# Environment-ArduinoNano44-Mini-Enclosure.net
KiCad netlist of a schematic drawn in EAGLE
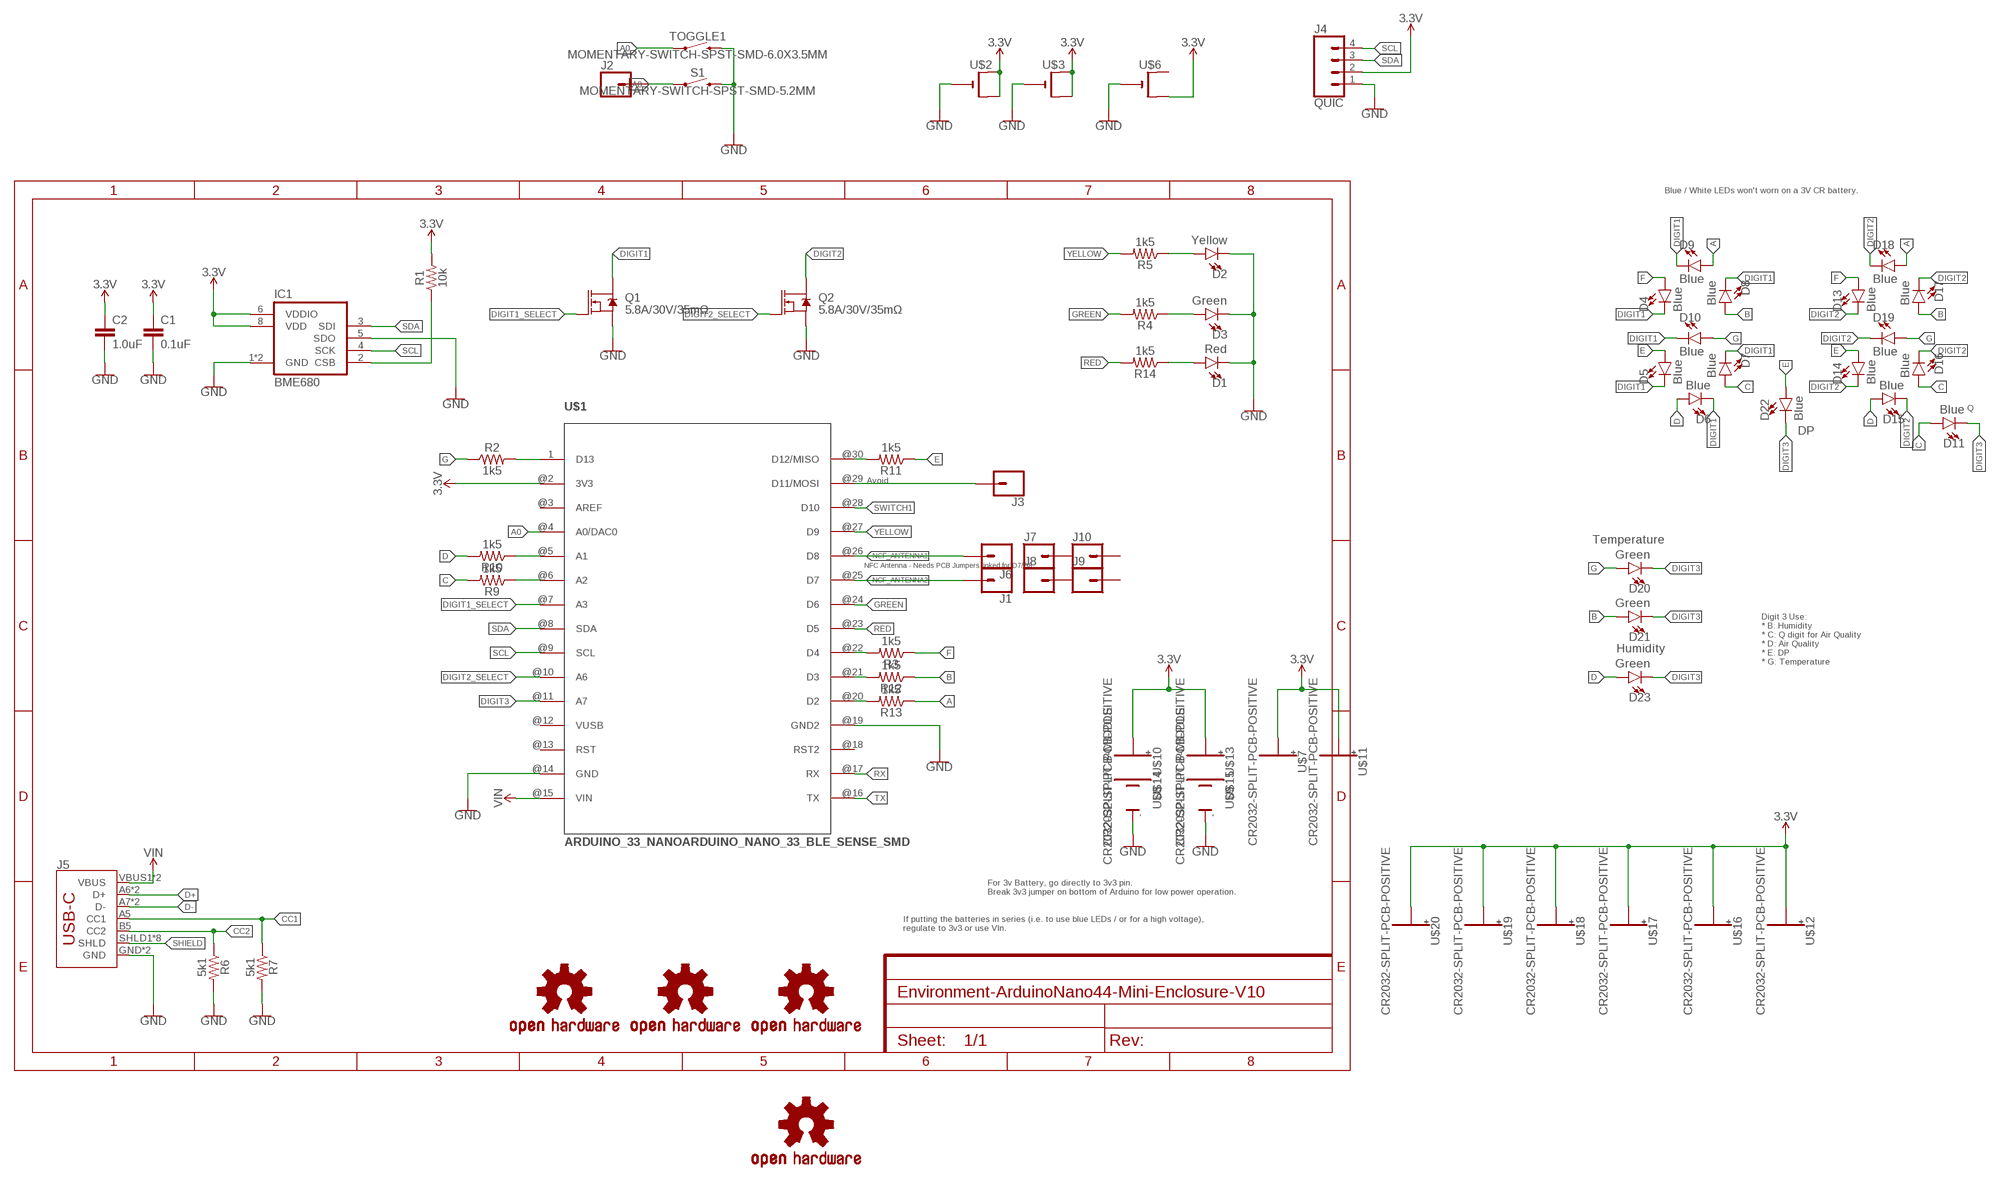
[diagram p0: schematic, sheet 1]

(export (version "E")
  (design (tool "Eeschema 10.0.6"))
  (components
    (comp (ref "C1")
      (value "0.1uF")
      (footprint "eagle-import:0805")
      (libsource (lib "eagle-import") (part "0.1UF-0805-25V"))
    )
    (comp (ref "C2")
      (value "1.0uF")
      (footprint "eagle-import:0805")
      (libsource (lib "eagle-import") (part "1.0UF-0805-25V-10%"))
    )
    (comp (ref "D1")
      (value "Red")
      (footprint "eagle-import:LED-1206")
      (libsource (lib "eagle-import") (part "LED1206"))
    )
    (comp (ref "D2")
      (value "Yellow")
      (footprint "eagle-import:LED-1206")
      (libsource (lib "eagle-import") (part "LED1206"))
    )
    (comp (ref "D3")
      (value "Green")
      (footprint "eagle-import:LED-1206")
      (libsource (lib "eagle-import") (part "LED1206"))
    )
    (comp (ref "D4")
      (value "Blue")
      (footprint "eagle-import:LED-1206")
      (libsource (lib "eagle-import") (part "LED1206"))
    )
    (comp (ref "D5")
      (value "Blue")
      (footprint "eagle-import:LED-1206")
      (libsource (lib "eagle-import") (part "LED1206"))
    )
    (comp (ref "D6")
      (value "Blue")
      (footprint "eagle-import:LED-1206")
      (libsource (lib "eagle-import") (part "LED1206"))
    )
    (comp (ref "D7")
      (value "Blue")
      (footprint "eagle-import:LED-1206")
      (libsource (lib "eagle-import") (part "LED1206"))
    )
    (comp (ref "D8")
      (value "Blue")
      (footprint "eagle-import:LED-1206")
      (libsource (lib "eagle-import") (part "LED1206"))
    )
    (comp (ref "D9")
      (value "Blue")
      (footprint "eagle-import:LED-1206")
      (libsource (lib "eagle-import") (part "LED1206"))
    )
    (comp (ref "D10")
      (value "Blue")
      (footprint "eagle-import:LED-1206")
      (libsource (lib "eagle-import") (part "LED1206"))
    )
    (comp (ref "D11")
      (value "Blue")
      (footprint "eagle-import:LED-1206")
      (libsource (lib "eagle-import") (part "LED1206"))
    )
    (comp (ref "D13")
      (value "Blue")
      (footprint "eagle-import:LED-1206")
      (libsource (lib "eagle-import") (part "LED1206"))
    )
    (comp (ref "D14")
      (value "Blue")
      (footprint "eagle-import:LED-1206")
      (libsource (lib "eagle-import") (part "LED1206"))
    )
    (comp (ref "D15")
      (value "Blue")
      (footprint "eagle-import:LED-1206")
      (libsource (lib "eagle-import") (part "LED1206"))
    )
    (comp (ref "D16")
      (value "Blue")
      (footprint "eagle-import:LED-1206")
      (libsource (lib "eagle-import") (part "LED1206"))
    )
    (comp (ref "D17")
      (value "Blue")
      (footprint "eagle-import:LED-1206")
      (libsource (lib "eagle-import") (part "LED1206"))
    )
    (comp (ref "D18")
      (value "Blue")
      (footprint "eagle-import:LED-1206")
      (libsource (lib "eagle-import") (part "LED1206"))
    )
    (comp (ref "D19")
      (value "Blue")
      (footprint "eagle-import:LED-1206")
      (libsource (lib "eagle-import") (part "LED1206"))
    )
    (comp (ref "D20")
      (value "Green")
      (footprint "eagle-import:LED-1206")
      (libsource (lib "eagle-import") (part "LED1206"))
    )
    (comp (ref "D21")
      (value "Green")
      (footprint "eagle-import:LED-1206")
      (libsource (lib "eagle-import") (part "LED1206"))
    )
    (comp (ref "D22")
      (value "Blue")
      (footprint "eagle-import:LED-1206")
      (libsource (lib "eagle-import") (part "LED1206"))
    )
    (comp (ref "D23")
      (value "Green")
      (footprint "eagle-import:LED-1206")
      (libsource (lib "eagle-import") (part "LED1206"))
    )
    (comp (ref "IC1")
      (value "BME680")
      (footprint "eagle-import:BME680")
      (libsource (lib "eagle-import") (part "BME680"))
    )
    (comp (ref "J1")
      (value "CONN_01")
      (footprint "eagle-import:1X01")
      (libsource (lib "eagle-import") (part "CONN_01"))
    )
    (comp (ref "J2")
      (value "CONN_01")
      (footprint "eagle-import:1X01")
      (libsource (lib "eagle-import") (part "CONN_01"))
    )
    (comp (ref "J3")
      (value "CONN_01")
      (footprint "eagle-import:1X01")
      (libsource (lib "eagle-import") (part "CONN_01"))
    )
    (comp (ref "J4")
      (value "QUIC")
      (footprint "eagle-import:JST04_1MM_RA")
      (libsource (lib "eagle-import") (part "CONN_04SMD2"))
    )
    (comp (ref "J5")
      (value "USB_C2-LAYER")
      (footprint "eagle-import:USB-C-16P")
      (libsource (lib "eagle-import") (part "USB_C2-LAYER"))
    )
    (comp (ref "J6")
      (value "CONN_01")
      (footprint "eagle-import:1X01")
      (libsource (lib "eagle-import") (part "CONN_01"))
    )
    (comp (ref "J7")
      (value "CONN_01")
      (footprint "eagle-import:1X01")
      (libsource (lib "eagle-import") (part "CONN_01"))
    )
    (comp (ref "J8")
      (value "CONN_01")
      (footprint "eagle-import:1X01")
      (libsource (lib "eagle-import") (part "CONN_01"))
    )
    (comp (ref "J9")
      (value "CONN_01")
      (footprint "eagle-import:1X01")
      (libsource (lib "eagle-import") (part "CONN_01"))
    )
    (comp (ref "J10")
      (value "CONN_01")
      (footprint "eagle-import:1X01")
      (libsource (lib "eagle-import") (part "CONN_01"))
    )
    (comp (ref "LOGO1")
      (value "OSHW-LOGOM")
      (footprint "eagle-import:OSHW-LOGO-M")
      (libsource (lib "eagle-import") (part "OSHW-LOGOM"))
    )
    (comp (ref "LOGO2")
      (value "OSHW-LOGOL")
      (footprint "eagle-import:OSHW-LOGO-L")
      (libsource (lib "eagle-import") (part "OSHW-LOGOL"))
    )
    (comp (ref "LOGO3")
      (value "OSHW-LOGOL")
      (footprint "eagle-import:OSHW-LOGO-L")
      (libsource (lib "eagle-import") (part "OSHW-LOGOL"))
    )
    (comp (ref "LOGO7")
      (value "OSHW-LOGOM")
      (footprint "eagle-import:OSHW-LOGO-M")
      (libsource (lib "eagle-import") (part "OSHW-LOGOM"))
    )
    (comp (ref "Q1")
      (value "5.8A/30V/35mΩ")
      (footprint "eagle-import:SOT23-3")
      (libsource (lib "eagle-import") (part "MOSFET-NCH-AO3404A"))
    )
    (comp (ref "Q2")
      (value "5.8A/30V/35mΩ")
      (footprint "eagle-import:SOT23-3")
      (libsource (lib "eagle-import") (part "MOSFET-NCH-AO3404A"))
    )
    (comp (ref "R1")
      (value "10k")
      (footprint "eagle-import:0805")
      (libsource (lib "eagle-import") (part "RESISTOR0805"))
    )
    (comp (ref "R2")
      (value "1k5")
      (footprint "eagle-import:0805")
      (libsource (lib "eagle-import") (part "RESISTOR0805"))
    )
    (comp (ref "R3")
      (value "1k5")
      (footprint "eagle-import:0805")
      (libsource (lib "eagle-import") (part "RESISTOR0805"))
    )
    (comp (ref "R4")
      (value "1k5")
      (footprint "eagle-import:0805")
      (libsource (lib "eagle-import") (part "RESISTOR0805"))
    )
    (comp (ref "R5")
      (value "1k5")
      (footprint "eagle-import:0805")
      (libsource (lib "eagle-import") (part "RESISTOR0805"))
    )
    (comp (ref "R6")
      (value "5k1")
      (footprint "eagle-import:0805")
      (libsource (lib "eagle-import") (part "RESISTOR0805"))
    )
    (comp (ref "R7")
      (value "5k1")
      (footprint "eagle-import:0805")
      (libsource (lib "eagle-import") (part "RESISTOR0805"))
    )
    (comp (ref "R9")
      (value "1k5")
      (footprint "eagle-import:0805")
      (libsource (lib "eagle-import") (part "RESISTOR0805"))
    )
    (comp (ref "R10")
      (value "1k5")
      (footprint "eagle-import:0805")
      (libsource (lib "eagle-import") (part "RESISTOR0805"))
    )
    (comp (ref "R11")
      (value "1k5")
      (footprint "eagle-import:0805")
      (libsource (lib "eagle-import") (part "RESISTOR0805"))
    )
    (comp (ref "R12")
      (value "1k5")
      (footprint "eagle-import:0805")
      (libsource (lib "eagle-import") (part "RESISTOR0805"))
    )
    (comp (ref "R13")
      (value "1k5")
      (footprint "eagle-import:0805")
      (libsource (lib "eagle-import") (part "RESISTOR0805"))
    )
    (comp (ref "R14")
      (value "1k5")
      (footprint "eagle-import:0805")
      (libsource (lib "eagle-import") (part "RESISTOR0805"))
    )
    (comp (ref "S1")
      (value "MOMENTARY-SWITCH-SPST-SMD-5.2MM")
      (footprint "eagle-import:TACTILE_SWITCH_SMD_5.2MM")
      (libsource (lib "eagle-import") (part "MOMENTARY-SWITCH-SPST-SMD-5.2MM"))
    )
    (comp (ref "TOGGLE1")
      (value "MOMENTARY-SWITCH-SPST-SMD-6.0X3.5MM")
      (footprint "eagle-import:TACTILE_SWITCH_SMD_6.0X3.5MM")
      (libsource (lib "eagle-import") (part "MOMENTARY-SWITCH-SPST-SMD-6.0X3.5MM"))
    )
    (comp (ref "U$1")
      (value "ARDUINO_33_NANOARDUINO_NANO_33_BLE_SENSE_SMD")
      (footprint "eagle-import:ARDUINO_NANO_33_SMD")
      (libsource (lib "eagle-import") (part "ARDUINO_33_NANOARDUINO_NANO_33_BLE_SENSE_SMD"))
    )
    (comp (ref "U$2")
      (value "CR2032SMT")
      (footprint "eagle-import:CR2032-SMD")
      (libsource (lib "eagle-import") (part "CR2032SMT"))
    )
    (comp (ref "U$3")
      (value "CR2032SMT")
      (footprint "eagle-import:CR2032-SMD")
      (libsource (lib "eagle-import") (part "CR2032SMT"))
    )
    (comp (ref "U$6")
      (value "CR2032SMT")
      (footprint "eagle-import:CR2032-SMD")
      (libsource (lib "eagle-import") (part "CR2032SMT"))
    )
    (comp (ref "U$7")
      (value "CR2032-SPLIT-PCB-POSITIVE")
      (footprint "eagle-import:CR2032-SMD-POSITIVE-TERMINAL")
      (libsource (lib "eagle-import") (part "CR2032-SPLIT-PCB-POSITIVE"))
    )
    (comp (ref "U$8")
      (value "CR2032-SPLIT-PCBCR2032-NEGATIVE")
      (footprint "eagle-import:CR2032-SMD-NEGATIVE-TERMINAL")
      (libsource (lib "eagle-import") (part "CR2032-SPLIT-PCBCR2032-NEGATIVE"))
    )
    (comp (ref "U$9")
      (value "CR2032-SPLIT-PCBCR2032-NEGATIVE")
      (footprint "eagle-import:CR2032-SMD-NEGATIVE-TERMINAL")
      (libsource (lib "eagle-import") (part "CR2032-SPLIT-PCBCR2032-NEGATIVE"))
    )
    (comp (ref "U$10")
      (value "CR2032-SPLIT-PCB-POSITIVE")
      (footprint "eagle-import:CR2032-SMD-POSITIVE-TERMINAL")
      (libsource (lib "eagle-import") (part "CR2032-SPLIT-PCB-POSITIVE"))
    )
    (comp (ref "U$11")
      (value "CR2032-SPLIT-PCB-POSITIVE")
      (footprint "eagle-import:CR2032-SMD-POSITIVE-TERMINAL")
      (libsource (lib "eagle-import") (part "CR2032-SPLIT-PCB-POSITIVE"))
    )
    (comp (ref "U$12")
      (value "CR2032-SPLIT-PCB-POSITIVE")
      (footprint "eagle-import:CR2032-SMD-POSITIVE-TERMINAL")
      (libsource (lib "eagle-import") (part "CR2032-SPLIT-PCB-POSITIVE"))
    )
    (comp (ref "U$13")
      (value "CR2032-SPLIT-PCB-POSITIVE")
      (footprint "eagle-import:CR2032-SMD-POSITIVE-TERMINAL")
      (libsource (lib "eagle-import") (part "CR2032-SPLIT-PCB-POSITIVE"))
    )
    (comp (ref "U$14")
      (value "CR2032-SPLIT-PCB-MIDDLE")
      (footprint "eagle-import:CR2032-SMD-MIDDLE-OUTLINE")
      (libsource (lib "eagle-import") (part "CR2032-SPLIT-PCB-MIDDLE"))
    )
    (comp (ref "U$15")
      (value "CR2032-SPLIT-PCB-MIDDLE")
      (footprint "eagle-import:CR2032-SMD-MIDDLE-OUTLINE")
      (libsource (lib "eagle-import") (part "CR2032-SPLIT-PCB-MIDDLE"))
    )
    (comp (ref "U$16")
      (value "CR2032-SPLIT-PCB-POSITIVE")
      (footprint "eagle-import:CR2032-SMD-POSITIVE-TERMINAL")
      (libsource (lib "eagle-import") (part "CR2032-SPLIT-PCB-POSITIVE"))
    )
    (comp (ref "U$17")
      (value "CR2032-SPLIT-PCB-POSITIVE")
      (footprint "eagle-import:CR2032-SMD-POSITIVE-TERMINAL")
      (libsource (lib "eagle-import") (part "CR2032-SPLIT-PCB-POSITIVE"))
    )
    (comp (ref "U$18")
      (value "CR2032-SPLIT-PCB-POSITIVE")
      (footprint "eagle-import:CR2032-SMD-POSITIVE-TERMINAL")
      (libsource (lib "eagle-import") (part "CR2032-SPLIT-PCB-POSITIVE"))
    )
    (comp (ref "U$19")
      (value "CR2032-SPLIT-PCB-POSITIVE")
      (footprint "eagle-import:CR2032-SMD-POSITIVE-TERMINAL")
      (libsource (lib "eagle-import") (part "CR2032-SPLIT-PCB-POSITIVE"))
    )
    (comp (ref "U$20")
      (value "CR2032-SPLIT-PCB-POSITIVE")
      (footprint "eagle-import:CR2032-SMD-POSITIVE-TERMINAL")
      (libsource (lib "eagle-import") (part "CR2032-SPLIT-PCB-POSITIVE"))
    )
  )
  (nets
    (net (code "1") (name "/VUSB") (class "Default")
      (node (ref "U$1") (pin "@12") (pinfunction "VUSB_@12") (pintype "power_in"))
    )
    (net (code "2") (name "3.3V") (class "Default")
      (node (ref "C1") (pin "1") (pinfunction "1_1") (pintype "passive"))
      (node (ref "C2") (pin "1") (pinfunction "1_1") (pintype "passive"))
      (node (ref "IC1") (pin "6") (pinfunction "VDDIO_6") (pintype "power_in"))
      (node (ref "IC1") (pin "8") (pinfunction "VDD_8") (pintype "power_in"))
      (node (ref "J4") (pin "2") (pinfunction "2_2") (pintype "passive"))
      (node (ref "R1") (pin "2") (pinfunction "2_2") (pintype "passive"))
      (node (ref "U$1") (pin "@2") (pinfunction "3V3_@2") (pintype "power_in"))
      (node (ref "U$10") (pin "+") (pinfunction "+_+") (pintype "power_in"))
      (node (ref "U$11") (pin "+") (pinfunction "+_+") (pintype "power_in"))
      (node (ref "U$12") (pin "+") (pinfunction "+_+") (pintype "power_in"))
      (node (ref "U$13") (pin "+") (pinfunction "+_+") (pintype "power_in"))
      (node (ref "U$16") (pin "+") (pinfunction "+_+") (pintype "power_in"))
      (node (ref "U$17") (pin "+") (pinfunction "+_+") (pintype "power_in"))
      (node (ref "U$18") (pin "+") (pinfunction "+_+") (pintype "power_in"))
      (node (ref "U$19") (pin "+") (pinfunction "+_+") (pintype "power_in"))
      (node (ref "U$2") (pin "+$1") (pinfunction "+_+$1") (pintype "passive"))
      (node (ref "U$2") (pin "+$2") (pinfunction "+1_+$2") (pintype "passive"))
      (node (ref "U$20") (pin "+") (pinfunction "+_+") (pintype "power_in"))
      (node (ref "U$3") (pin "+$1") (pinfunction "+_+$1") (pintype "passive"))
      (node (ref "U$3") (pin "+$2") (pinfunction "+1_+$2") (pintype "passive"))
      (node (ref "U$6") (pin "+$2") (pinfunction "+1_+$2") (pintype "passive"))
      (node (ref "U$7") (pin "+") (pinfunction "+_+") (pintype "power_in"))
    )
    (net (code "3") (name "A") (class "Default")
      (node (ref "D18") (pin "A") (pinfunction "A_A") (pintype "passive"))
      (node (ref "D9") (pin "A") (pinfunction "A_A") (pintype "passive"))
      (node (ref "R13") (pin "1") (pinfunction "1_1") (pintype "passive"))
    )
    (net (code "4") (name "A0") (class "Default")
      (node (ref "J2") (pin "1") (pinfunction "1_1") (pintype "passive"))
      (node (ref "S1") (pin "1") (pinfunction "1_1") (pintype "passive"))
      (node (ref "TOGGLE1") (pin "1") (pinfunction "1_1") (pintype "passive"))
      (node (ref "U$1") (pin "@4") (pinfunction "A0/DAC0_@4") (pintype "bidirectional"))
    )
    (net (code "5") (name "B") (class "Default")
      (node (ref "D17") (pin "A") (pinfunction "A_A") (pintype "passive"))
      (node (ref "D21") (pin "A") (pinfunction "A_A") (pintype "passive"))
      (node (ref "D8") (pin "A") (pinfunction "A_A") (pintype "passive"))
      (node (ref "R12") (pin "1") (pinfunction "1_1") (pintype "passive"))
    )
    (net (code "6") (name "C") (class "Default")
      (node (ref "D11") (pin "A") (pinfunction "A_A") (pintype "passive"))
      (node (ref "D16") (pin "A") (pinfunction "A_A") (pintype "passive"))
      (node (ref "D7") (pin "A") (pinfunction "A_A") (pintype "passive"))
      (node (ref "R9") (pin "2") (pinfunction "2_2") (pintype "passive"))
    )
    (net (code "7") (name "CC1") (class "Default")
      (node (ref "J5") (pin "A5") (pinfunction "CC1_A5") (pintype "bidirectional"))
      (node (ref "R7") (pin "1") (pinfunction "1_1") (pintype "passive"))
    )
    (net (code "8") (name "CC2") (class "Default")
      (node (ref "J5") (pin "B5") (pinfunction "CC2_B5") (pintype "bidirectional"))
      (node (ref "R6") (pin "1") (pinfunction "1_1") (pintype "passive"))
    )
    (net (code "9") (name "D") (class "Default")
      (node (ref "D15") (pin "A") (pinfunction "A_A") (pintype "passive"))
      (node (ref "D23") (pin "A") (pinfunction "A_A") (pintype "passive"))
      (node (ref "D6") (pin "A") (pinfunction "A_A") (pintype "passive"))
      (node (ref "R10") (pin "2") (pinfunction "2_2") (pintype "passive"))
    )
    (net (code "10") (name "D+") (class "Default")
      (node (ref "J5") (pin "A6") (pinfunction "D+_A6") (pintype "bidirectional"))
      (node (ref "J5") (pin "B6") (pinfunction "D+_B6") (pintype "bidirectional"))
    )
    (net (code "11") (name "D-") (class "Default")
      (node (ref "J5") (pin "A7") (pinfunction "D-_A7") (pintype "bidirectional"))
      (node (ref "J5") (pin "B7") (pinfunction "D-_B7") (pintype "bidirectional"))
    )
    (net (code "12") (name "DIGIT1") (class "Default")
      (node (ref "D10") (pin "C") (pinfunction "C_C") (pintype "passive"))
      (node (ref "D4") (pin "C") (pinfunction "C_C") (pintype "passive"))
      (node (ref "D5") (pin "C") (pinfunction "C_C") (pintype "passive"))
      (node (ref "D6") (pin "C") (pinfunction "C_C") (pintype "passive"))
      (node (ref "D7") (pin "C") (pinfunction "C_C") (pintype "passive"))
      (node (ref "D8") (pin "C") (pinfunction "C_C") (pintype "passive"))
      (node (ref "D9") (pin "C") (pinfunction "C_C") (pintype "passive"))
      (node (ref "Q1") (pin "3") (pinfunction "D_3") (pintype "bidirectional"))
    )
    (net (code "13") (name "DIGIT1_SELECT") (class "Default")
      (node (ref "Q1") (pin "1") (pinfunction "G_1") (pintype "bidirectional"))
      (node (ref "U$1") (pin "@7") (pinfunction "A3_@7") (pintype "bidirectional"))
    )
    (net (code "14") (name "DIGIT2") (class "Default")
      (node (ref "D13") (pin "C") (pinfunction "C_C") (pintype "passive"))
      (node (ref "D14") (pin "C") (pinfunction "C_C") (pintype "passive"))
      (node (ref "D15") (pin "C") (pinfunction "C_C") (pintype "passive"))
      (node (ref "D16") (pin "C") (pinfunction "C_C") (pintype "passive"))
      (node (ref "D17") (pin "C") (pinfunction "C_C") (pintype "passive"))
      (node (ref "D18") (pin "C") (pinfunction "C_C") (pintype "passive"))
      (node (ref "D19") (pin "C") (pinfunction "C_C") (pintype "passive"))
      (node (ref "Q2") (pin "3") (pinfunction "D_3") (pintype "bidirectional"))
    )
    (net (code "15") (name "DIGIT2_SELECT") (class "Default")
      (node (ref "Q2") (pin "1") (pinfunction "G_1") (pintype "bidirectional"))
      (node (ref "U$1") (pin "@10") (pinfunction "A6_@10") (pintype "bidirectional"))
    )
    (net (code "16") (name "DIGIT3") (class "Default")
      (node (ref "D11") (pin "C") (pinfunction "C_C") (pintype "passive"))
      (node (ref "D20") (pin "C") (pinfunction "C_C") (pintype "passive"))
      (node (ref "D21") (pin "C") (pinfunction "C_C") (pintype "passive"))
      (node (ref "D22") (pin "C") (pinfunction "C_C") (pintype "passive"))
      (node (ref "D23") (pin "C") (pinfunction "C_C") (pintype "passive"))
      (node (ref "U$1") (pin "@11") (pinfunction "A7_@11") (pintype "bidirectional"))
    )
    (net (code "17") (name "E") (class "Default")
      (node (ref "D14") (pin "A") (pinfunction "A_A") (pintype "passive"))
      (node (ref "D22") (pin "A") (pinfunction "A_A") (pintype "passive"))
      (node (ref "D5") (pin "A") (pinfunction "A_A") (pintype "passive"))
      (node (ref "R11") (pin "1") (pinfunction "1_1") (pintype "passive"))
    )
    (net (code "18") (name "F") (class "Default")
      (node (ref "D13") (pin "A") (pinfunction "A_A") (pintype "passive"))
      (node (ref "D4") (pin "A") (pinfunction "A_A") (pintype "passive"))
      (node (ref "R3") (pin "1") (pinfunction "1_1") (pintype "passive"))
    )
    (net (code "19") (name "G") (class "Default")
      (node (ref "D10") (pin "A") (pinfunction "A_A") (pintype "passive"))
      (node (ref "D19") (pin "A") (pinfunction "A_A") (pintype "passive"))
      (node (ref "D20") (pin "A") (pinfunction "A_A") (pintype "passive"))
      (node (ref "R2") (pin "1") (pinfunction "1_1") (pintype "passive"))
    )
    (net (code "20") (name "GND") (class "Default")
      (node (ref "C1") (pin "2") (pinfunction "2_2") (pintype "passive"))
      (node (ref "C2") (pin "2") (pinfunction "2_2") (pintype "passive"))
      (node (ref "D1") (pin "C") (pinfunction "C_C") (pintype "passive"))
      (node (ref "D2") (pin "C") (pinfunction "C_C") (pintype "passive"))
      (node (ref "D3") (pin "C") (pinfunction "C_C") (pintype "passive"))
      (node (ref "IC1") (pin "1") (pinfunction "GND_1") (pintype "power_in"))
      (node (ref "IC1") (pin "5") (pinfunction "SDO_5") (pintype "output"))
      (node (ref "IC1") (pin "7") (pinfunction "GND_7") (pintype "power_in"))
      (node (ref "J4") (pin "1") (pinfunction "1_1") (pintype "passive"))
      (node (ref "J5") (pin "GND") (pinfunction "GND_GND") (pintype "bidirectional"))
      (node (ref "J5") (pin "GND2") (pinfunction "GND_GND2") (pintype "bidirectional"))
      (node (ref "Q1") (pin "2") (pinfunction "S_2") (pintype "bidirectional"))
      (node (ref "Q2") (pin "2") (pinfunction "S_2") (pintype "bidirectional"))
      (node (ref "R6") (pin "2") (pinfunction "2_2") (pintype "passive"))
      (node (ref "R7") (pin "2") (pinfunction "2_2") (pintype "passive"))
      (node (ref "S1") (pin "3") (pinfunction "2_3") (pintype "passive"))
      (node (ref "TOGGLE1") (pin "2") (pinfunction "2_2") (pintype "passive"))
      (node (ref "U$1") (pin "@14") (pinfunction "GND_@14") (pintype "bidirectional"))
      (node (ref "U$1") (pin "@19") (pinfunction "GND2_@19") (pintype "bidirectional"))
      (node (ref "U$2") (pin "-") (pinfunction "-_-") (pintype "passive"))
      (node (ref "U$3") (pin "-") (pinfunction "-_-") (pintype "passive"))
      (node (ref "U$6") (pin "-") (pinfunction "-_-") (pintype "passive"))
      (node (ref "U$8") (pin "-") (pinfunction "-_-") (pintype "power_in"))
      (node (ref "U$9") (pin "-") (pinfunction "-_-") (pintype "power_in"))
    )
    (net (code "21") (name "GREEN") (class "Default")
      (node (ref "R4") (pin "2") (pinfunction "2_2") (pintype "passive"))
      (node (ref "U$1") (pin "@24") (pinfunction "D6_@24") (pintype "bidirectional"))
    )
    (net (code "22") (name "NCF_ANTENNA1") (class "Default")
      (node (ref "J6") (pin "1") (pinfunction "1_1") (pintype "passive"))
      (node (ref "U$1") (pin "@26") (pinfunction "D8_@26") (pintype "bidirectional"))
    )
    (net (code "23") (name "NCF_ANTENNA2") (class "Default")
      (node (ref "J1") (pin "1") (pinfunction "1_1") (pintype "passive"))
      (node (ref "U$1") (pin "@25") (pinfunction "D7_@25") (pintype "bidirectional"))
    )
    (net (code "24") (name "Net-(D1-PadA)") (class "Default")
      (node (ref "D1") (pin "A") (pinfunction "A_A") (pintype "passive"))
      (node (ref "R14") (pin "1") (pinfunction "1_1") (pintype "passive"))
    )
    (net (code "25") (name "Net-(D2-PadA)") (class "Default")
      (node (ref "D2") (pin "A") (pinfunction "A_A") (pintype "passive"))
      (node (ref "R5") (pin "1") (pinfunction "1_1") (pintype "passive"))
    )
    (net (code "26") (name "Net-(D3-PadA)") (class "Default")
      (node (ref "D3") (pin "A") (pinfunction "A_A") (pintype "passive"))
      (node (ref "R4") (pin "1") (pinfunction "1_1") (pintype "passive"))
    )
    (net (code "27") (name "Net-(IC1-CSB)") (class "Default")
      (node (ref "IC1") (pin "2") (pinfunction "CSB_2") (pintype "input"))
      (node (ref "R1") (pin "1") (pinfunction "1_1") (pintype "passive"))
    )
    (net (code "28") (name "Net-(U$1-A1)") (class "Default")
      (node (ref "R10") (pin "1") (pinfunction "1_1") (pintype "passive"))
      (node (ref "U$1") (pin "@5") (pinfunction "A1_@5") (pintype "bidirectional"))
    )
    (net (code "29") (name "Net-(U$1-A2)") (class "Default")
      (node (ref "R9") (pin "1") (pinfunction "1_1") (pintype "passive"))
      (node (ref "U$1") (pin "@6") (pinfunction "A2_@6") (pintype "bidirectional"))
    )
    (net (code "30") (name "Net-(U$1-D2)") (class "Default")
      (node (ref "R13") (pin "2") (pinfunction "2_2") (pintype "passive"))
      (node (ref "U$1") (pin "@20") (pinfunction "D2_@20") (pintype "bidirectional"))
    )
    (net (code "31") (name "Net-(U$1-D3)") (class "Default")
      (node (ref "R12") (pin "2") (pinfunction "2_2") (pintype "passive"))
      (node (ref "U$1") (pin "@21") (pinfunction "D3_@21") (pintype "bidirectional"))
    )
    (net (code "32") (name "Net-(U$1-D4)") (class "Default")
      (node (ref "R3") (pin "2") (pinfunction "2_2") (pintype "passive"))
      (node (ref "U$1") (pin "@22") (pinfunction "D4_@22") (pintype "bidirectional"))
    )
    (net (code "33") (name "Net-(U$1-D11{slash}MOSI)") (class "Default")
      (node (ref "J3") (pin "1") (pinfunction "1_1") (pintype "passive"))
      (node (ref "U$1") (pin "@29") (pinfunction "D11/MOSI_@29") (pintype "bidirectional"))
    )
    (net (code "34") (name "Net-(U$1-D12{slash}MISO)") (class "Default")
      (node (ref "R11") (pin "2") (pinfunction "2_2") (pintype "passive"))
      (node (ref "U$1") (pin "@30") (pinfunction "D12/MISO_@30") (pintype "bidirectional"))
    )
    (net (code "35") (name "Net-(U$1-D13)") (class "Default")
      (node (ref "R2") (pin "2") (pinfunction "2_2") (pintype "passive"))
      (node (ref "U$1") (pin "1") (pinfunction "D13_1") (pintype "bidirectional"))
    )
    (net (code "36") (name "RED") (class "Default")
      (node (ref "R14") (pin "2") (pinfunction "2_2") (pintype "passive"))
      (node (ref "U$1") (pin "@23") (pinfunction "D5_@23") (pintype "bidirectional"))
    )
    (net (code "37") (name "RX") (class "Default")
      (node (ref "U$1") (pin "@17") (pinfunction "RX_@17") (pintype "bidirectional"))
    )
    (net (code "38") (name "SCL") (class "Default")
      (node (ref "IC1") (pin "4") (pinfunction "SCK_4") (pintype "input"))
      (node (ref "J4") (pin "4") (pinfunction "4_4") (pintype "passive"))
      (node (ref "U$1") (pin "@9") (pinfunction "SCL_@9") (pintype "bidirectional"))
    )
    (net (code "39") (name "SDA") (class "Default")
      (node (ref "IC1") (pin "3") (pinfunction "SDI_3") (pintype "input"))
      (node (ref "J4") (pin "3") (pinfunction "3_3") (pintype "passive"))
      (node (ref "U$1") (pin "@8") (pinfunction "SDA_@8") (pintype "bidirectional"))
    )
    (net (code "40") (name "SHIELD") (class "Default")
      (node (ref "J5") (pin "SHLD1") (pinfunction "SHLD_SHLD1") (pintype "bidirectional"))
      (node (ref "J5") (pin "SHLD2") (pinfunction "SHLD_SHLD2") (pintype "bidirectional"))
      (node (ref "J5") (pin "SHLD3") (pinfunction "SHLD_SHLD3") (pintype "bidirectional"))
      (node (ref "J5") (pin "SHLD4") (pinfunction "SHLD_SHLD4") (pintype "bidirectional"))
      (node (ref "J5") (pin "SHLD5") (pinfunction "SHLD_SHLD5") (pintype "bidirectional"))
      (node (ref "J5") (pin "SHLD6") (pinfunction "SHLD_SHLD6") (pintype "bidirectional"))
      (node (ref "J5") (pin "SHLD7") (pinfunction "SHLD_SHLD7") (pintype "bidirectional"))
      (node (ref "J5") (pin "SHLD8") (pinfunction "SHLD_SHLD8") (pintype "bidirectional"))
    )
    (net (code "41") (name "SWITCH1") (class "Default")
      (node (ref "U$1") (pin "@28") (pinfunction "D10_@28") (pintype "bidirectional"))
    )
    (net (code "42") (name "TX") (class "Default")
      (node (ref "U$1") (pin "@16") (pinfunction "TX_@16") (pintype "bidirectional"))
    )
    (net (code "43") (name "VIN") (class "Default")
      (node (ref "J5") (pin "VBUS1") (pinfunction "VBUS_VBUS1") (pintype "bidirectional"))
      (node (ref "J5") (pin "VBUS2") (pinfunction "VBUS_VBUS2") (pintype "bidirectional"))
      (node (ref "U$1") (pin "@15") (pinfunction "VIN_@15") (pintype "power_in"))
    )
    (net (code "44") (name "YELLOW") (class "Default")
      (node (ref "R5") (pin "2") (pinfunction "2_2") (pintype "passive"))
      (node (ref "U$1") (pin "@27") (pinfunction "D9_@27") (pintype "bidirectional"))
    )
    (net (code "45") (name "unconnected-(J7-Pad1)") (class "Default")
      (node (ref "J7") (pin "1") (pinfunction "1_1") (pintype "passive"))
    )
    (net (code "46") (name "unconnected-(J8-Pad1)") (class "Default")
      (node (ref "J8") (pin "1") (pinfunction "1_1") (pintype "passive"))
    )
    (net (code "47") (name "unconnected-(J9-Pad1)") (class "Default")
      (node (ref "J9") (pin "1") (pinfunction "1_1") (pintype "passive"))
    )
    (net (code "48") (name "unconnected-(J10-Pad1)") (class "Default")
      (node (ref "J10") (pin "1") (pinfunction "1_1") (pintype "passive"))
    )
    (net (code "49") (name "unconnected-(U$1-AREF-Pad@3)") (class "Default")
      (node (ref "U$1") (pin "@3") (pinfunction "AREF_@3") (pintype "output"))
    )
    (net (code "50") (name "unconnected-(U$1-RST-Pad@13)") (class "Default")
      (node (ref "U$1") (pin "@13") (pinfunction "RST_@13") (pintype "bidirectional"))
    )
    (net (code "51") (name "unconnected-(U$1-RST2-Pad@18)") (class "Default")
      (node (ref "U$1") (pin "@18") (pinfunction "RST2_@18") (pintype "bidirectional"))
    )
    (net (code "52") (name "unconnected-(U$6-+-Pad+$1)") (class "Default")
      (node (ref "U$6") (pin "+$1") (pinfunction "+_+$1") (pintype "passive"))
    )
  )
)
